# H-Bridge-no_enable.net
KiCad netlist of a schematic drawn in EAGLE
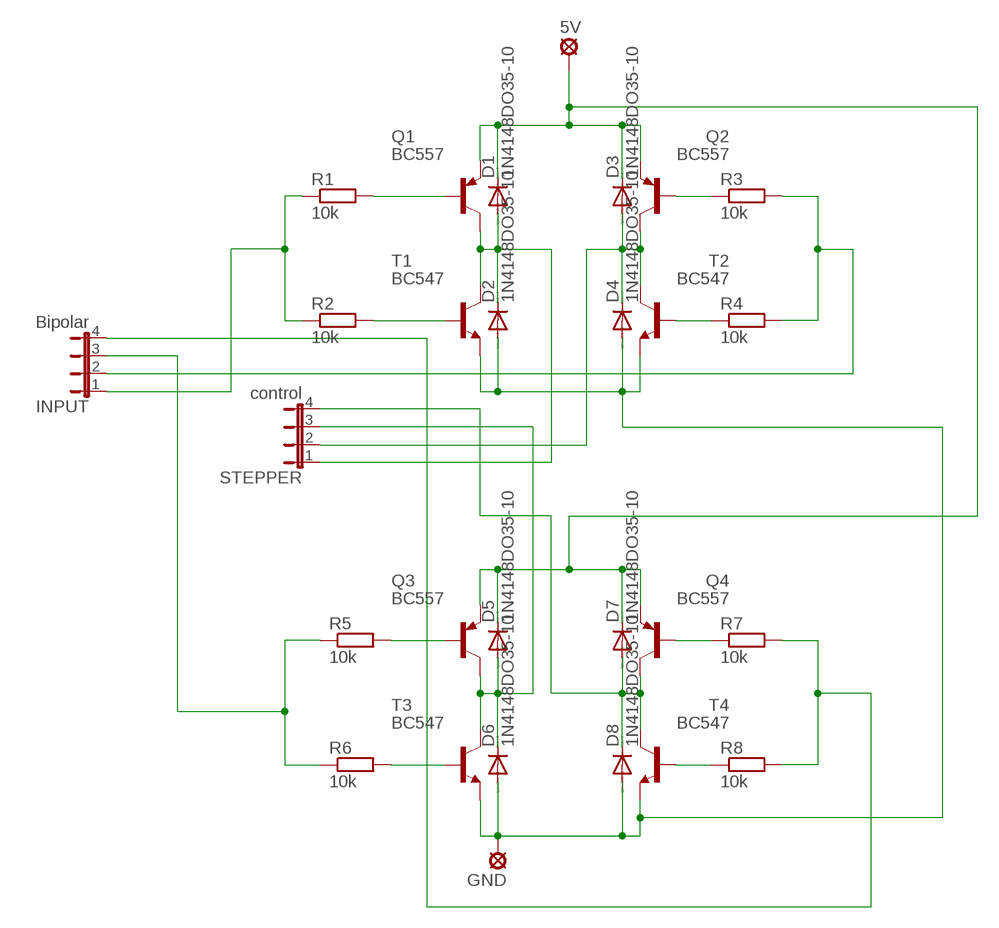
[diagram p0: schematic, sheet 1]

(export (version "E")
  (design (tool "Eeschema 10.0.6"))
  (components
    (comp (ref "5V")
      (value "LSP10")
      (footprint "eagle-import:LSP10")
      (libsource (lib "eagle-import") (part "LSP10"))
    )
    (comp (ref "D1")
      (value "1N4148DO35-10")
      (footprint "eagle-import:DO35-10")
      (libsource (lib "eagle-import") (part "1N4148DO35-10"))
    )
    (comp (ref "D2")
      (value "1N4148DO35-10")
      (footprint "eagle-import:DO35-10")
      (libsource (lib "eagle-import") (part "1N4148DO35-10"))
    )
    (comp (ref "D3")
      (value "1N4148DO35-10")
      (footprint "eagle-import:DO35-10")
      (libsource (lib "eagle-import") (part "1N4148DO35-10"))
    )
    (comp (ref "D4")
      (value "1N4148DO35-10")
      (footprint "eagle-import:DO35-10")
      (libsource (lib "eagle-import") (part "1N4148DO35-10"))
    )
    (comp (ref "D5")
      (value "1N4148DO35-10")
      (footprint "eagle-import:DO35-10")
      (libsource (lib "eagle-import") (part "1N4148DO35-10"))
    )
    (comp (ref "D6")
      (value "1N4148DO35-10")
      (footprint "eagle-import:DO35-10")
      (libsource (lib "eagle-import") (part "1N4148DO35-10"))
    )
    (comp (ref "D7")
      (value "1N4148DO35-10")
      (footprint "eagle-import:DO35-10")
      (libsource (lib "eagle-import") (part "1N4148DO35-10"))
    )
    (comp (ref "D8")
      (value "1N4148DO35-10")
      (footprint "eagle-import:DO35-10")
      (libsource (lib "eagle-import") (part "1N4148DO35-10"))
    )
    (comp (ref "GND")
      (value "LSP10")
      (footprint "eagle-import:LSP10")
      (libsource (lib "eagle-import") (part "LSP10"))
    )
    (comp (ref "INPUT")
      (value "Bipolar")
      (footprint "eagle-import:JP4")
      (libsource (lib "eagle-import") (part "JP4E"))
    )
    (comp (ref "Q1")
      (value "BC557")
      (footprint "eagle-import:TO92")
      (libsource (lib "eagle-import") (part "BC557"))
    )
    (comp (ref "Q2")
      (value "BC557")
      (footprint "eagle-import:TO92")
      (libsource (lib "eagle-import") (part "BC557"))
    )
    (comp (ref "Q3")
      (value "BC557")
      (footprint "eagle-import:TO92")
      (libsource (lib "eagle-import") (part "BC557"))
    )
    (comp (ref "Q4")
      (value "BC557")
      (footprint "eagle-import:TO92")
      (libsource (lib "eagle-import") (part "BC557"))
    )
    (comp (ref "R1")
      (value "10k")
      (footprint "eagle-import:0204V")
      (libsource (lib "eagle-import") (part "R-EU_0204/2V"))
    )
    (comp (ref "R2")
      (value "10k")
      (footprint "eagle-import:0204V")
      (libsource (lib "eagle-import") (part "R-EU_0204/2V"))
    )
    (comp (ref "R3")
      (value "10k")
      (footprint "eagle-import:0204V")
      (libsource (lib "eagle-import") (part "R-EU_0204/2V"))
    )
    (comp (ref "R4")
      (value "10k")
      (footprint "eagle-import:0204V")
      (libsource (lib "eagle-import") (part "R-EU_0204/2V"))
    )
    (comp (ref "R5")
      (value "10k")
      (footprint "eagle-import:0204V")
      (libsource (lib "eagle-import") (part "R-EU_0204/2V"))
    )
    (comp (ref "R6")
      (value "10k")
      (footprint "eagle-import:0204V")
      (libsource (lib "eagle-import") (part "R-EU_0204/2V"))
    )
    (comp (ref "R7")
      (value "10k")
      (footprint "eagle-import:0204V")
      (libsource (lib "eagle-import") (part "R-EU_0204/2V"))
    )
    (comp (ref "R8")
      (value "10k")
      (footprint "eagle-import:0204V")
      (libsource (lib "eagle-import") (part "R-EU_0204/2V"))
    )
    (comp (ref "STEPPER")
      (value "control")
      (footprint "eagle-import:JP4")
      (libsource (lib "eagle-import") (part "JP4E"))
    )
    (comp (ref "T1")
      (value "BC547")
      (footprint "eagle-import:TO92")
      (libsource (lib "eagle-import") (part "BC547"))
    )
    (comp (ref "T2")
      (value "BC547")
      (footprint "eagle-import:TO92")
      (libsource (lib "eagle-import") (part "BC547"))
    )
    (comp (ref "T3")
      (value "BC547")
      (footprint "eagle-import:TO92")
      (libsource (lib "eagle-import") (part "BC547"))
    )
    (comp (ref "T4")
      (value "BC547")
      (footprint "eagle-import:TO92")
      (libsource (lib "eagle-import") (part "BC547"))
    )
  )
  (nets
    (net (code "1") (name "Net-(INPUT-Pad1)") (class "Default")
      (node (ref "INPUT") (pin "1") (pinfunction "1_1") (pintype "passive"))
      (node (ref "R1") (pin "1") (pinfunction "1_1") (pintype "passive"))
      (node (ref "R2") (pin "1") (pinfunction "1_1") (pintype "passive"))
    )
    (net (code "2") (name "Net-(INPUT-Pad2)") (class "Default")
      (node (ref "INPUT") (pin "2") (pinfunction "2_2") (pintype "passive"))
      (node (ref "R3") (pin "2") (pinfunction "2_2") (pintype "passive"))
      (node (ref "R4") (pin "2") (pinfunction "2_2") (pintype "passive"))
    )
    (net (code "3") (name "Net-(INPUT-Pad3)") (class "Default")
      (node (ref "INPUT") (pin "3") (pinfunction "3_3") (pintype "passive"))
      (node (ref "R5") (pin "1") (pinfunction "1_1") (pintype "passive"))
      (node (ref "R6") (pin "1") (pinfunction "1_1") (pintype "passive"))
    )
    (net (code "4") (name "Net-(INPUT-Pad4)") (class "Default")
      (node (ref "INPUT") (pin "4") (pinfunction "4_4") (pintype "passive"))
      (node (ref "R7") (pin "2") (pinfunction "2_2") (pintype "passive"))
      (node (ref "R8") (pin "2") (pinfunction "2_2") (pintype "passive"))
    )
    (net (code "5") (name "Net-(Q1-B)") (class "Default")
      (node (ref "Q1") (pin "2") (pinfunction "B_2") (pintype "passive"))
      (node (ref "R1") (pin "2") (pinfunction "2_2") (pintype "passive"))
    )
    (net (code "6") (name "Net-(Q1-C)") (class "Default")
      (node (ref "D1") (pin "A") (pinfunction "A_A") (pintype "passive"))
      (node (ref "D2") (pin "C") (pinfunction "C_C") (pintype "passive"))
      (node (ref "Q1") (pin "3") (pinfunction "C_3") (pintype "passive"))
      (node (ref "STEPPER") (pin "1") (pinfunction "1_1") (pintype "passive"))
      (node (ref "T1") (pin "3") (pinfunction "C_3") (pintype "passive"))
    )
    (net (code "7") (name "Net-(Q1-E)") (class "Default")
      (node (ref "5V") (pin "MP") (pinfunction "MP_MP") (pintype "passive"))
      (node (ref "D1") (pin "C") (pinfunction "C_C") (pintype "passive"))
      (node (ref "D3") (pin "C") (pinfunction "C_C") (pintype "passive"))
      (node (ref "D5") (pin "C") (pinfunction "C_C") (pintype "passive"))
      (node (ref "D7") (pin "C") (pinfunction "C_C") (pintype "passive"))
      (node (ref "Q1") (pin "1") (pinfunction "E_1") (pintype "passive"))
      (node (ref "Q2") (pin "1") (pinfunction "E_1") (pintype "passive"))
      (node (ref "Q3") (pin "1") (pinfunction "E_1") (pintype "passive"))
      (node (ref "Q4") (pin "1") (pinfunction "E_1") (pintype "passive"))
    )
    (net (code "8") (name "Net-(Q2-B)") (class "Default")
      (node (ref "Q2") (pin "2") (pinfunction "B_2") (pintype "passive"))
      (node (ref "R3") (pin "1") (pinfunction "1_1") (pintype "passive"))
    )
    (net (code "9") (name "Net-(Q2-C)") (class "Default")
      (node (ref "D3") (pin "A") (pinfunction "A_A") (pintype "passive"))
      (node (ref "D4") (pin "C") (pinfunction "C_C") (pintype "passive"))
      (node (ref "Q2") (pin "3") (pinfunction "C_3") (pintype "passive"))
      (node (ref "STEPPER") (pin "2") (pinfunction "2_2") (pintype "passive"))
      (node (ref "T2") (pin "3") (pinfunction "C_3") (pintype "passive"))
    )
    (net (code "10") (name "Net-(Q3-B)") (class "Default")
      (node (ref "Q3") (pin "2") (pinfunction "B_2") (pintype "passive"))
      (node (ref "R5") (pin "2") (pinfunction "2_2") (pintype "passive"))
    )
    (net (code "11") (name "Net-(Q3-C)") (class "Default")
      (node (ref "D5") (pin "A") (pinfunction "A_A") (pintype "passive"))
      (node (ref "D6") (pin "C") (pinfunction "C_C") (pintype "passive"))
      (node (ref "Q3") (pin "3") (pinfunction "C_3") (pintype "passive"))
      (node (ref "STEPPER") (pin "3") (pinfunction "3_3") (pintype "passive"))
      (node (ref "T3") (pin "3") (pinfunction "C_3") (pintype "passive"))
    )
    (net (code "12") (name "Net-(Q4-B)") (class "Default")
      (node (ref "Q4") (pin "2") (pinfunction "B_2") (pintype "passive"))
      (node (ref "R7") (pin "1") (pinfunction "1_1") (pintype "passive"))
    )
    (net (code "13") (name "Net-(Q4-C)") (class "Default")
      (node (ref "D7") (pin "A") (pinfunction "A_A") (pintype "passive"))
      (node (ref "D8") (pin "C") (pinfunction "C_C") (pintype "passive"))
      (node (ref "Q4") (pin "3") (pinfunction "C_3") (pintype "passive"))
      (node (ref "STEPPER") (pin "4") (pinfunction "4_4") (pintype "passive"))
      (node (ref "T4") (pin "3") (pinfunction "C_3") (pintype "passive"))
    )
    (net (code "14") (name "Net-(T1-B)") (class "Default")
      (node (ref "R2") (pin "2") (pinfunction "2_2") (pintype "passive"))
      (node (ref "T1") (pin "2") (pinfunction "B_2") (pintype "passive"))
    )
    (net (code "15") (name "Net-(T1-E)") (class "Default")
      (node (ref "D2") (pin "A") (pinfunction "A_A") (pintype "passive"))
      (node (ref "D4") (pin "A") (pinfunction "A_A") (pintype "passive"))
      (node (ref "D6") (pin "A") (pinfunction "A_A") (pintype "passive"))
      (node (ref "D8") (pin "A") (pinfunction "A_A") (pintype "passive"))
      (node (ref "GND") (pin "MP") (pinfunction "MP_MP") (pintype "passive"))
      (node (ref "T1") (pin "1") (pinfunction "E_1") (pintype "passive"))
      (node (ref "T2") (pin "1") (pinfunction "E_1") (pintype "passive"))
      (node (ref "T3") (pin "1") (pinfunction "E_1") (pintype "passive"))
      (node (ref "T4") (pin "1") (pinfunction "E_1") (pintype "passive"))
    )
    (net (code "16") (name "Net-(T2-B)") (class "Default")
      (node (ref "R4") (pin "1") (pinfunction "1_1") (pintype "passive"))
      (node (ref "T2") (pin "2") (pinfunction "B_2") (pintype "passive"))
    )
    (net (code "17") (name "Net-(T3-B)") (class "Default")
      (node (ref "R6") (pin "2") (pinfunction "2_2") (pintype "passive"))
      (node (ref "T3") (pin "2") (pinfunction "B_2") (pintype "passive"))
    )
    (net (code "18") (name "Net-(T4-B)") (class "Default")
      (node (ref "R8") (pin "1") (pinfunction "1_1") (pintype "passive"))
      (node (ref "T4") (pin "2") (pinfunction "B_2") (pintype "passive"))
    )
  )
)
